# Gecko-Node.net
KiCad netlist of a schematic drawn in EAGLE
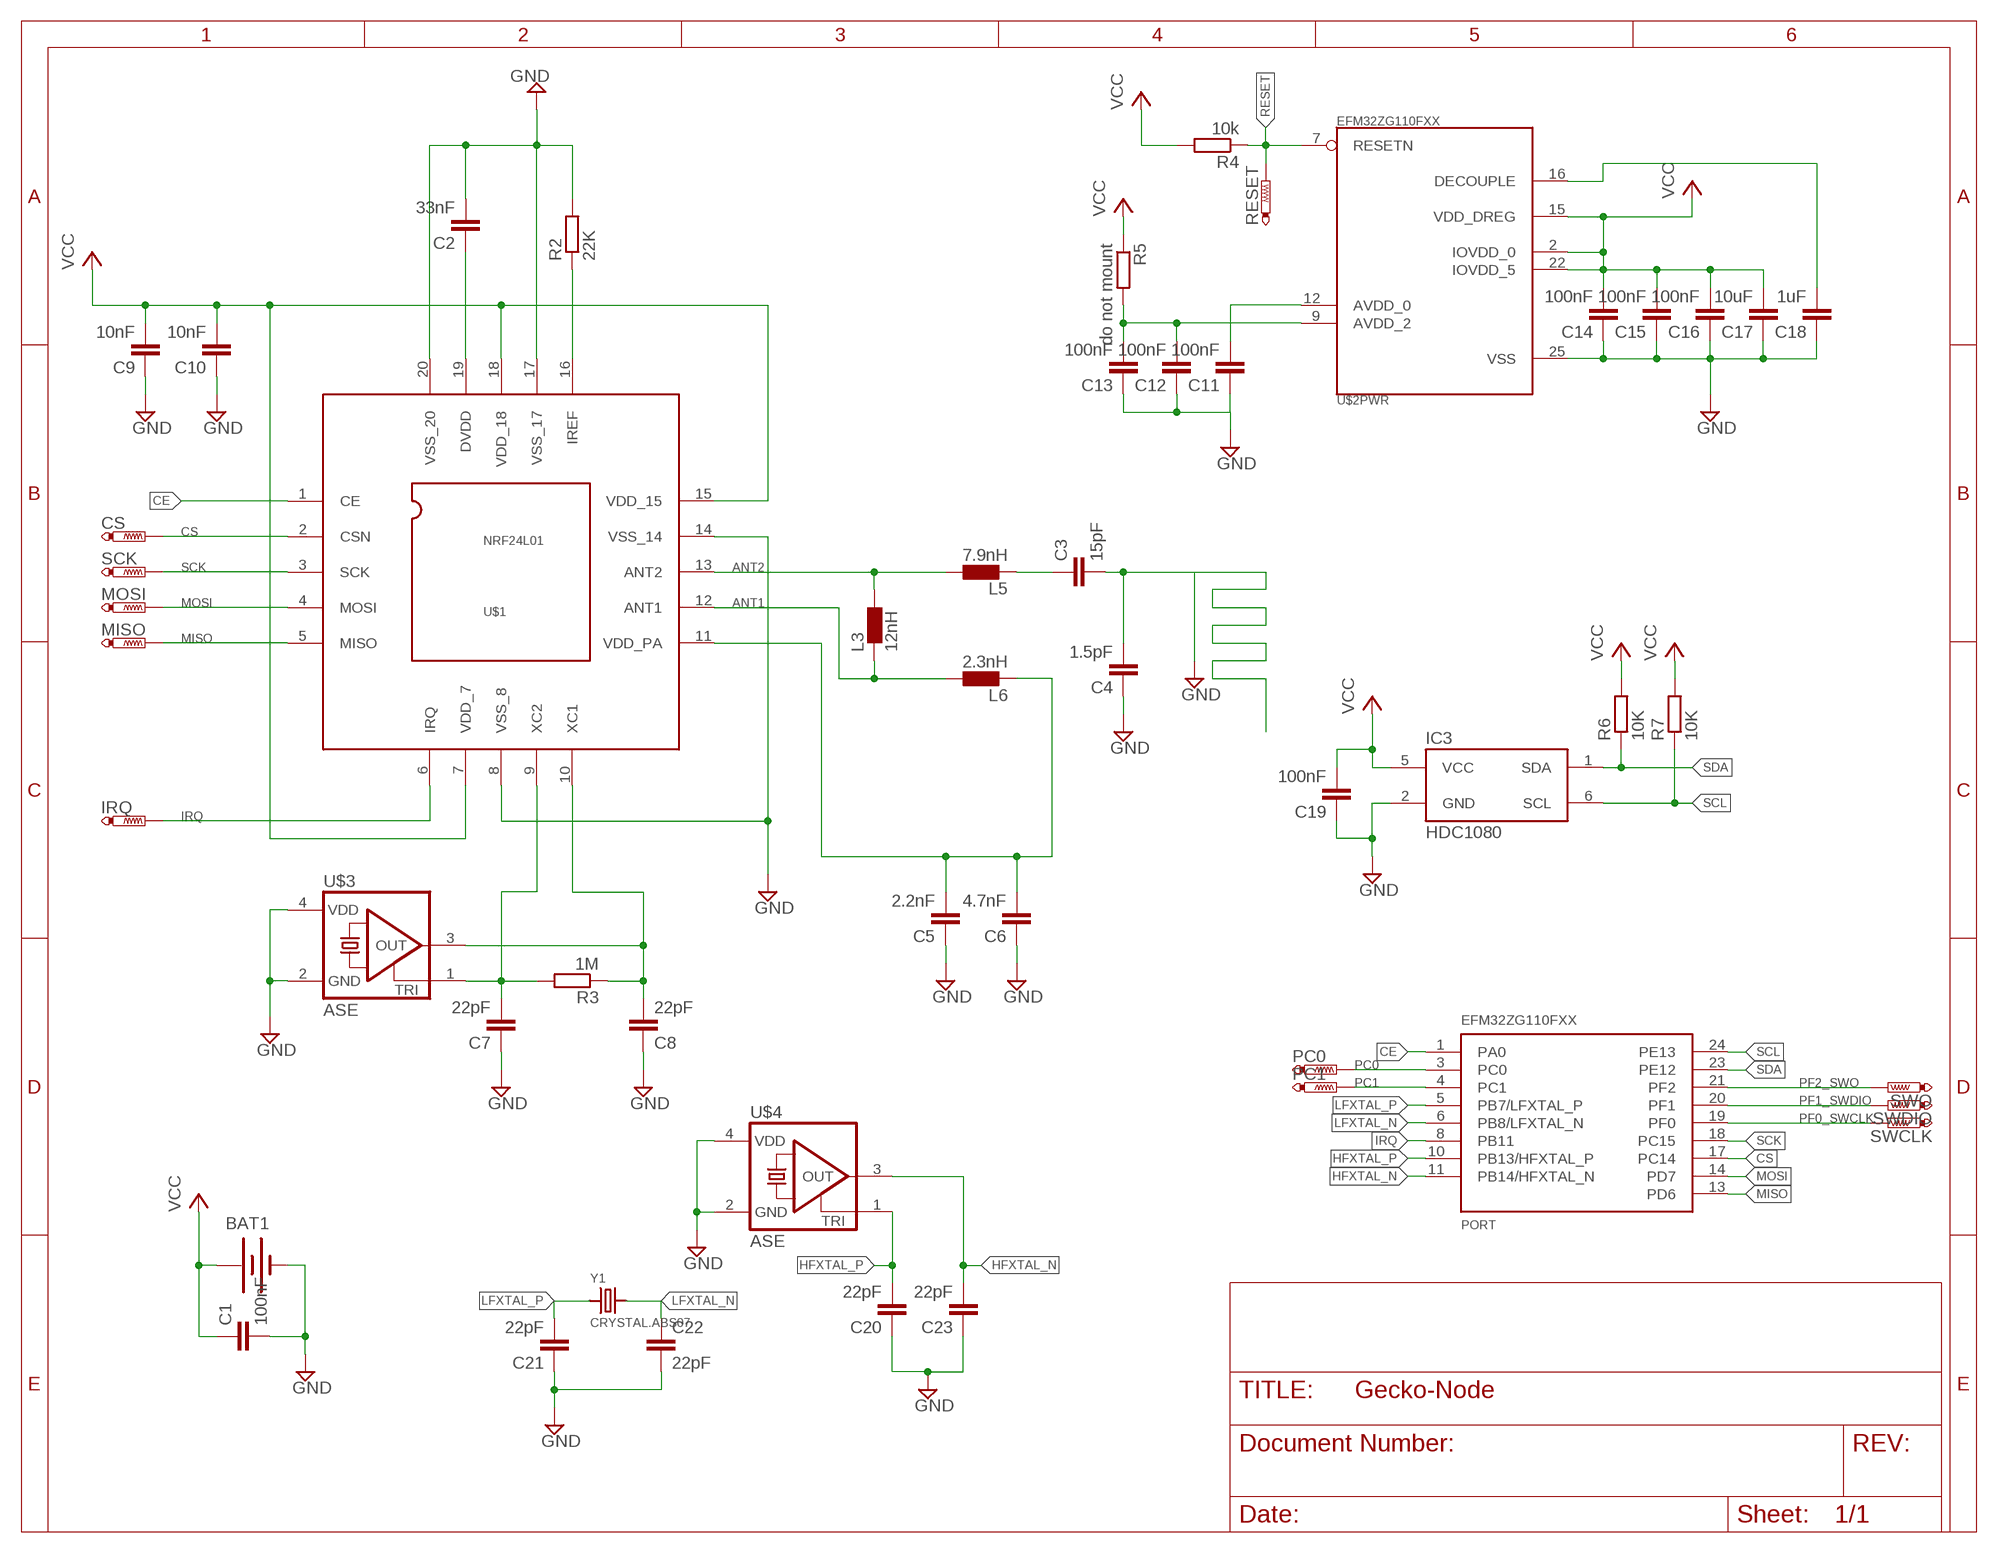
[diagram p0: schematic, sheet 1]

(export (version "E")
  (design (tool "Eeschema 10.0.6"))
  (components
    (comp (ref "BAT1")
      (value "LINX-BAT-HLD-00120SMD")
      (footprint "eagle-import:BATTCON_20MM")
      (libsource (lib "eagle-import") (part "LINX-BAT-HLD-00120SMD"))
    )
    (comp (ref "C1")
      (value "100nF")
      (footprint "eagle-import:C0603")
      (libsource (lib "eagle-import") (part "C-EUC0603"))
    )
    (comp (ref "C2")
      (value "33nF")
      (footprint "eagle-import:C0603")
      (libsource (lib "eagle-import") (part "C-EUC0603"))
    )
    (comp (ref "C3")
      (value "15pF")
      (footprint "eagle-import:C0603")
      (libsource (lib "eagle-import") (part "C-EUC0603"))
    )
    (comp (ref "C4")
      (value "1.5pF")
      (footprint "eagle-import:C0603")
      (libsource (lib "eagle-import") (part "C-EUC0603"))
    )
    (comp (ref "C5")
      (value "2.2nF")
      (footprint "eagle-import:C0603")
      (libsource (lib "eagle-import") (part "C-EUC0603"))
    )
    (comp (ref "C6")
      (value "4.7nF")
      (footprint "eagle-import:C0603")
      (libsource (lib "eagle-import") (part "C-EUC0603"))
    )
    (comp (ref "C7")
      (value "22pF")
      (footprint "eagle-import:C0603")
      (libsource (lib "eagle-import") (part "C-EUC0603"))
    )
    (comp (ref "C8")
      (value "22pF")
      (footprint "eagle-import:C0603")
      (libsource (lib "eagle-import") (part "C-EUC0603"))
    )
    (comp (ref "C9")
      (value "10nF")
      (footprint "eagle-import:C0603")
      (libsource (lib "eagle-import") (part "C-EUC0603"))
    )
    (comp (ref "C10")
      (value "10nF")
      (footprint "eagle-import:C0603")
      (libsource (lib "eagle-import") (part "C-EUC0603"))
    )
    (comp (ref "C11")
      (value "100nF")
      (footprint "eagle-import:C0603")
      (libsource (lib "eagle-import") (part "C-EUC0603"))
    )
    (comp (ref "C12")
      (value "100nF")
      (footprint "eagle-import:C0603")
      (libsource (lib "eagle-import") (part "C-EUC0603"))
    )
    (comp (ref "C13")
      (value "100nF")
      (footprint "eagle-import:C0603")
      (libsource (lib "eagle-import") (part "C-EUC0603"))
    )
    (comp (ref "C14")
      (value "100nF")
      (footprint "eagle-import:C0603")
      (libsource (lib "eagle-import") (part "C-EUC0603"))
    )
    (comp (ref "C15")
      (value "100nF")
      (footprint "eagle-import:C0603")
      (libsource (lib "eagle-import") (part "C-EUC0603"))
    )
    (comp (ref "C16")
      (value "100nF")
      (footprint "eagle-import:C0603")
      (libsource (lib "eagle-import") (part "C-EUC0603"))
    )
    (comp (ref "C17")
      (value "10uF")
      (footprint "eagle-import:C0603")
      (libsource (lib "eagle-import") (part "C-EUC0603"))
    )
    (comp (ref "C18")
      (value "1uF")
      (footprint "eagle-import:C0603")
      (libsource (lib "eagle-import") (part "C-EUC0603"))
    )
    (comp (ref "C19")
      (value "100nF")
      (footprint "eagle-import:C0603")
      (libsource (lib "eagle-import") (part "C-EUC0603"))
    )
    (comp (ref "C20")
      (value "22pF")
      (footprint "eagle-import:C0603")
      (libsource (lib "eagle-import") (part "C-EUC0603"))
    )
    (comp (ref "C21")
      (value "22pF")
      (footprint "eagle-import:C0603")
      (libsource (lib "eagle-import") (part "C-EUC0603"))
    )
    (comp (ref "C22")
      (value "22pF")
      (footprint "eagle-import:C0603")
      (libsource (lib "eagle-import") (part "C-EUC0603"))
    )
    (comp (ref "C23")
      (value "22pF")
      (footprint "eagle-import:C0603")
      (libsource (lib "eagle-import") (part "C-EUC0603"))
    )
    (comp (ref "CS")
      (value "PTR1TP08R")
      (footprint "eagle-import:TP08R")
      (libsource (lib "eagle-import") (part "PTR1TP08R"))
    )
    (comp (ref "IC3")
      (value "HDC1080")
      (footprint "eagle-import:WSON6")
      (libsource (lib "eagle-import") (part "HDC1080"))
    )
    (comp (ref "IRQ")
      (value "PTR1TP08R")
      (footprint "eagle-import:TP08R")
      (libsource (lib "eagle-import") (part "PTR1TP08R"))
    )
    (comp (ref "L3")
      (value "12nH")
      (footprint "eagle-import:R0603")
      (libsource (lib "eagle-import") (part "L"))
    )
    (comp (ref "L5")
      (value "7.9nH")
      (footprint "eagle-import:R0603")
      (libsource (lib "eagle-import") (part "L"))
    )
    (comp (ref "L6")
      (value "2.3nH")
      (footprint "eagle-import:R0603")
      (libsource (lib "eagle-import") (part "L"))
    )
    (comp (ref "MISO")
      (value "PTR1TP08R")
      (footprint "eagle-import:TP08R")
      (libsource (lib "eagle-import") (part "PTR1TP08R"))
    )
    (comp (ref "MOSI")
      (value "PTR1TP08R")
      (footprint "eagle-import:TP08R")
      (libsource (lib "eagle-import") (part "PTR1TP08R"))
    )
    (comp (ref "PC0")
      (value "PTR1TP08R")
      (footprint "eagle-import:TP08R")
      (libsource (lib "eagle-import") (part "PTR1TP08R"))
    )
    (comp (ref "PC1")
      (value "PTR1TP08R")
      (footprint "eagle-import:TP08R")
      (libsource (lib "eagle-import") (part "PTR1TP08R"))
    )
    (comp (ref "R2")
      (value "22K")
      (footprint "eagle-import:R0603")
      (libsource (lib "eagle-import") (part "R-EU_R0603"))
    )
    (comp (ref "R3")
      (value "1M")
      (footprint "eagle-import:R0603")
      (libsource (lib "eagle-import") (part "R-EU_R0603"))
    )
    (comp (ref "R4")
      (value "10k")
      (footprint "eagle-import:R0603")
      (libsource (lib "eagle-import") (part "R-EU_R0603"))
    )
    (comp (ref "R5")
      (value "do not mount")
      (footprint "eagle-import:R0603")
      (libsource (lib "eagle-import") (part "R-EU_R0603"))
    )
    (comp (ref "R6")
      (value "10K")
      (footprint "eagle-import:R0603")
      (libsource (lib "eagle-import") (part "R-EU_R0603"))
    )
    (comp (ref "R7")
      (value "10K")
      (footprint "eagle-import:R0603")
      (libsource (lib "eagle-import") (part "R-EU_R0603"))
    )
    (comp (ref "RESET")
      (value "PTR1TP08R")
      (footprint "eagle-import:TP08R")
      (libsource (lib "eagle-import") (part "PTR1TP08R"))
    )
    (comp (ref "SCK")
      (value "PTR1TP08R")
      (footprint "eagle-import:TP08R")
      (libsource (lib "eagle-import") (part "PTR1TP08R"))
    )
    (comp (ref "SWCLK")
      (value "PTR1TP08R")
      (footprint "eagle-import:TP08R")
      (libsource (lib "eagle-import") (part "PTR1TP08R"))
    )
    (comp (ref "SWDIO")
      (value "PTR1TP08R")
      (footprint "eagle-import:TP08R")
      (libsource (lib "eagle-import") (part "PTR1TP08R"))
    )
    (comp (ref "SWO")
      (value "PTR1TP08R")
      (footprint "eagle-import:TP08R")
      (libsource (lib "eagle-import") (part "PTR1TP08R"))
    )
    (comp (ref "U$1")
      (value "NRF24L01")
      (footprint "eagle-import:QFN20")
      (libsource (lib "eagle-import") (part "NRF24L01"))
    )
    (comp (ref "U$2")
      (value "EFM32ZG110FXX")
      (footprint "eagle-import:QFN24")
      (libsource (lib "eagle-import") (part "EFM32ZG110FXX"))
    )
    (comp (ref "U$3")
      (value "ASE")
      (footprint "eagle-import:ASE")
      (libsource (lib "eagle-import") (part "ASE"))
    )
    (comp (ref "U$4")
      (value "ASE")
      (footprint "eagle-import:ASE")
      (libsource (lib "eagle-import") (part "ASE"))
    )
    (comp (ref "Y1")
      (value "CRYSTAL.ABS07")
      (footprint "eagle-import:ABS07")
      (libsource (lib "eagle-import") (part "CRYSTAL.ABS07"))
    )
  )
  (nets
    (net (code "1") (name "/ANT1") (class "Default")
      (node (ref "L3") (pin "2") (pinfunction "2_2") (pintype "passive"))
      (node (ref "L6") (pin "1") (pinfunction "1_1") (pintype "passive"))
      (node (ref "U$1") (pin "12") (pinfunction "ANT1_12") (pintype "bidirectional"))
    )
    (net (code "2") (name "/ANT2") (class "Default")
      (node (ref "L3") (pin "1") (pinfunction "1_1") (pintype "passive"))
      (node (ref "L5") (pin "1") (pinfunction "1_1") (pintype "passive"))
      (node (ref "U$1") (pin "13") (pinfunction "ANT2_13") (pintype "bidirectional"))
    )
    (net (code "3") (name "/PC0") (class "Default")
      (node (ref "PC0") (pin "TP") (pinfunction "TP_TP") (pintype "input"))
      (node (ref "U$2") (pin "3") (pinfunction "PC0_3") (pintype "bidirectional"))
    )
    (net (code "4") (name "/PC1") (class "Default")
      (node (ref "PC1") (pin "TP") (pinfunction "TP_TP") (pintype "input"))
      (node (ref "U$2") (pin "4") (pinfunction "PC1_4") (pintype "bidirectional"))
    )
    (net (code "5") (name "/PF0_SWCLK") (class "Default")
      (node (ref "SWCLK") (pin "TP") (pinfunction "TP_TP") (pintype "input"))
      (node (ref "U$2") (pin "19") (pinfunction "PF0_19") (pintype "bidirectional"))
    )
    (net (code "6") (name "/PF1_SWDIO") (class "Default")
      (node (ref "SWDIO") (pin "TP") (pinfunction "TP_TP") (pintype "input"))
      (node (ref "U$2") (pin "20") (pinfunction "PF1_20") (pintype "bidirectional"))
    )
    (net (code "7") (name "/PF2_SWO") (class "Default")
      (node (ref "SWO") (pin "TP") (pinfunction "TP_TP") (pintype "input"))
      (node (ref "U$2") (pin "21") (pinfunction "PF2_21") (pintype "bidirectional"))
    )
    (net (code "8") (name "CE") (class "Default")
      (node (ref "U$1") (pin "1") (pinfunction "CE_1") (pintype "bidirectional"))
      (node (ref "U$2") (pin "1") (pinfunction "PA0_1") (pintype "bidirectional"))
    )
    (net (code "9") (name "CS") (class "Default")
      (node (ref "CS") (pin "TP") (pinfunction "TP_TP") (pintype "input"))
      (node (ref "U$1") (pin "2") (pinfunction "CSN_2") (pintype "bidirectional"))
      (node (ref "U$2") (pin "17") (pinfunction "PC14_17") (pintype "bidirectional"))
    )
    (net (code "10") (name "GND") (class "Default")
      (node (ref "BAT1") (pin "2") (pinfunction "-_2") (pintype "power_in"))
      (node (ref "C1") (pin "2") (pinfunction "2_2") (pintype "passive"))
      (node (ref "C10") (pin "1") (pinfunction "1_1") (pintype "passive"))
      (node (ref "C11") (pin "1") (pinfunction "1_1") (pintype "passive"))
      (node (ref "C12") (pin "1") (pinfunction "1_1") (pintype "passive"))
      (node (ref "C13") (pin "1") (pinfunction "1_1") (pintype "passive"))
      (node (ref "C14") (pin "1") (pinfunction "1_1") (pintype "passive"))
      (node (ref "C15") (pin "1") (pinfunction "1_1") (pintype "passive"))
      (node (ref "C16") (pin "1") (pinfunction "1_1") (pintype "passive"))
      (node (ref "C17") (pin "1") (pinfunction "1_1") (pintype "passive"))
      (node (ref "C18") (pin "1") (pinfunction "1_1") (pintype "passive"))
      (node (ref "C19") (pin "1") (pinfunction "1_1") (pintype "passive"))
      (node (ref "C2") (pin "2") (pinfunction "2_2") (pintype "passive"))
      (node (ref "C20") (pin "1") (pinfunction "1_1") (pintype "passive"))
      (node (ref "C21") (pin "1") (pinfunction "1_1") (pintype "passive"))
      (node (ref "C22") (pin "2") (pinfunction "2_2") (pintype "passive"))
      (node (ref "C23") (pin "1") (pinfunction "1_1") (pintype "passive"))
      (node (ref "C3") (pin "2") (pinfunction "2_2") (pintype "passive"))
      (node (ref "C4") (pin "1") (pinfunction "1_1") (pintype "passive"))
      (node (ref "C4") (pin "2") (pinfunction "2_2") (pintype "passive"))
      (node (ref "C5") (pin "1") (pinfunction "1_1") (pintype "passive"))
      (node (ref "C6") (pin "1") (pinfunction "1_1") (pintype "passive"))
      (node (ref "C7") (pin "1") (pinfunction "1_1") (pintype "passive"))
      (node (ref "C8") (pin "1") (pinfunction "1_1") (pintype "passive"))
      (node (ref "C9") (pin "1") (pinfunction "1_1") (pintype "passive"))
      (node (ref "IC3") (pin "2") (pinfunction "GND_2") (pintype "power_in"))
      (node (ref "R2") (pin "2") (pinfunction "2_2") (pintype "passive"))
      (node (ref "U$1") (pin "14") (pinfunction "VSS_14_14") (pintype "bidirectional"))
      (node (ref "U$1") (pin "17") (pinfunction "VSS_17_17") (pintype "bidirectional"))
      (node (ref "U$1") (pin "20") (pinfunction "VSS_20_20") (pintype "bidirectional"))
      (node (ref "U$1") (pin "8") (pinfunction "VSS_8_8") (pintype "bidirectional"))
      (node (ref "U$2") (pin "25") (pinfunction "VSS_25") (pintype "power_in"))
      (node (ref "U$3") (pin "2") (pinfunction "GND_2") (pintype "power_in"))
      (node (ref "U$3") (pin "4") (pinfunction "VDD_4") (pintype "power_in"))
      (node (ref "U$4") (pin "2") (pinfunction "GND_2") (pintype "power_in"))
      (node (ref "U$4") (pin "4") (pinfunction "VDD_4") (pintype "power_in"))
    )
    (net (code "11") (name "HFXTAL_N") (class "Default")
      (node (ref "C23") (pin "2") (pinfunction "2_2") (pintype "passive"))
      (node (ref "U$2") (pin "11") (pinfunction "PB14/HFXTAL_N_11") (pintype "bidirectional"))
      (node (ref "U$4") (pin "3") (pinfunction "OUT_3") (pintype "output"))
    )
    (net (code "12") (name "HFXTAL_P") (class "Default")
      (node (ref "C20") (pin "2") (pinfunction "2_2") (pintype "passive"))
      (node (ref "U$2") (pin "10") (pinfunction "PB13/HFXTAL_P_10") (pintype "bidirectional"))
      (node (ref "U$4") (pin "1") (pinfunction "TRI_1") (pintype "input"))
    )
    (net (code "13") (name "IRQ") (class "Default")
      (node (ref "IRQ") (pin "TP") (pinfunction "TP_TP") (pintype "input"))
      (node (ref "U$1") (pin "6") (pinfunction "IRQ_6") (pintype "bidirectional"))
      (node (ref "U$2") (pin "8") (pinfunction "PB11_8") (pintype "bidirectional"))
    )
    (net (code "14") (name "LFXTAL_N") (class "Default")
      (node (ref "C22") (pin "1") (pinfunction "1_1") (pintype "passive"))
      (node (ref "U$2") (pin "6") (pinfunction "PB8/LFXTAL_N_6") (pintype "bidirectional"))
      (node (ref "Y1") (pin "2") (pinfunction "2_2") (pintype "passive"))
    )
    (net (code "15") (name "LFXTAL_P") (class "Default")
      (node (ref "C21") (pin "2") (pinfunction "2_2") (pintype "passive"))
      (node (ref "U$2") (pin "5") (pinfunction "PB7/LFXTAL_P_5") (pintype "bidirectional"))
      (node (ref "Y1") (pin "1") (pinfunction "1_1") (pintype "passive"))
    )
    (net (code "16") (name "MISO") (class "Default")
      (node (ref "MISO") (pin "TP") (pinfunction "TP_TP") (pintype "input"))
      (node (ref "U$1") (pin "5") (pinfunction "MISO_5") (pintype "bidirectional"))
      (node (ref "U$2") (pin "13") (pinfunction "PD6_13") (pintype "bidirectional"))
    )
    (net (code "17") (name "MOSI") (class "Default")
      (node (ref "MOSI") (pin "TP") (pinfunction "TP_TP") (pintype "input"))
      (node (ref "U$1") (pin "4") (pinfunction "MOSI_4") (pintype "bidirectional"))
      (node (ref "U$2") (pin "14") (pinfunction "PD7_14") (pintype "bidirectional"))
    )
    (net (code "18") (name "Net-(C3-Pad1)") (class "Default")
      (node (ref "C3") (pin "1") (pinfunction "1_1") (pintype "passive"))
      (node (ref "L5") (pin "2") (pinfunction "2_2") (pintype "passive"))
    )
    (net (code "19") (name "Net-(U$1-DVDD)") (class "Default")
      (node (ref "C2") (pin "1") (pinfunction "1_1") (pintype "passive"))
      (node (ref "U$1") (pin "19") (pinfunction "DVDD_19") (pintype "bidirectional"))
    )
    (net (code "20") (name "Net-(U$1-IREF)") (class "Default")
      (node (ref "R2") (pin "1") (pinfunction "1_1") (pintype "passive"))
      (node (ref "U$1") (pin "16") (pinfunction "IREF_16") (pintype "bidirectional"))
    )
    (net (code "21") (name "Net-(U$1-VDD_PA)") (class "Default")
      (node (ref "C5") (pin "2") (pinfunction "2_2") (pintype "passive"))
      (node (ref "C6") (pin "2") (pinfunction "2_2") (pintype "passive"))
      (node (ref "L6") (pin "2") (pinfunction "2_2") (pintype "passive"))
      (node (ref "U$1") (pin "11") (pinfunction "VDD_PA_11") (pintype "bidirectional"))
    )
    (net (code "22") (name "Net-(U$1-XC1)") (class "Default")
      (node (ref "C8") (pin "2") (pinfunction "2_2") (pintype "passive"))
      (node (ref "R3") (pin "1") (pinfunction "1_1") (pintype "passive"))
      (node (ref "U$1") (pin "10") (pinfunction "XC1_10") (pintype "bidirectional"))
      (node (ref "U$3") (pin "3") (pinfunction "OUT_3") (pintype "output"))
    )
    (net (code "23") (name "Net-(U$1-XC2)") (class "Default")
      (node (ref "C7") (pin "2") (pinfunction "2_2") (pintype "passive"))
      (node (ref "R3") (pin "2") (pinfunction "2_2") (pintype "passive"))
      (node (ref "U$1") (pin "9") (pinfunction "XC2_9") (pintype "bidirectional"))
      (node (ref "U$3") (pin "1") (pinfunction "TRI_1") (pintype "input"))
    )
    (net (code "24") (name "Net-(U$2B-AVDD_0)") (class "Default")
      (node (ref "C11") (pin "2") (pinfunction "2_2") (pintype "passive"))
      (node (ref "U$2") (pin "12") (pinfunction "AVDD_0_12") (pintype "power_in"))
    )
    (net (code "25") (name "Net-(U$2B-AVDD_2)") (class "Default")
      (node (ref "C12") (pin "2") (pinfunction "2_2") (pintype "passive"))
      (node (ref "C13") (pin "2") (pinfunction "2_2") (pintype "passive"))
      (node (ref "R5") (pin "2") (pinfunction "2_2") (pintype "passive"))
      (node (ref "U$2") (pin "9") (pinfunction "AVDD_2_9") (pintype "power_in"))
    )
    (net (code "26") (name "Net-(U$2B-DECOUPLE)") (class "Default")
      (node (ref "C18") (pin "2") (pinfunction "2_2") (pintype "passive"))
      (node (ref "U$2") (pin "16") (pinfunction "DECOUPLE_16") (pintype "power_in"))
    )
    (net (code "27") (name "RESET") (class "Default")
      (node (ref "R4") (pin "1") (pinfunction "1_1") (pintype "passive"))
      (node (ref "RESET") (pin "TP") (pinfunction "TP_TP") (pintype "input"))
      (node (ref "U$2") (pin "7") (pinfunction "RESETN_7") (pintype "passive"))
    )
    (net (code "28") (name "SCK") (class "Default")
      (node (ref "SCK") (pin "TP") (pinfunction "TP_TP") (pintype "input"))
      (node (ref "U$1") (pin "3") (pinfunction "SCK_3") (pintype "bidirectional"))
      (node (ref "U$2") (pin "18") (pinfunction "PC15_18") (pintype "bidirectional"))
    )
    (net (code "29") (name "SCL") (class "Default")
      (node (ref "IC3") (pin "6") (pinfunction "SCL_6") (pintype "bidirectional"))
      (node (ref "R7") (pin "1") (pinfunction "1_1") (pintype "passive"))
      (node (ref "U$2") (pin "24") (pinfunction "PE13_24") (pintype "bidirectional"))
    )
    (net (code "30") (name "SDA") (class "Default")
      (node (ref "IC3") (pin "1") (pinfunction "SDA_1") (pintype "bidirectional"))
      (node (ref "R6") (pin "1") (pinfunction "1_1") (pintype "passive"))
      (node (ref "U$2") (pin "23") (pinfunction "PE12_23") (pintype "bidirectional"))
    )
    (net (code "31") (name "VCC") (class "Default")
      (node (ref "BAT1") (pin "1") (pinfunction "+_1") (pintype "power_in"))
      (node (ref "BAT1") (pin "3") (pinfunction "+_3") (pintype "power_in"))
      (node (ref "C1") (pin "1") (pinfunction "1_1") (pintype "passive"))
      (node (ref "C10") (pin "2") (pinfunction "2_2") (pintype "passive"))
      (node (ref "C14") (pin "2") (pinfunction "2_2") (pintype "passive"))
      (node (ref "C15") (pin "2") (pinfunction "2_2") (pintype "passive"))
      (node (ref "C16") (pin "2") (pinfunction "2_2") (pintype "passive"))
      (node (ref "C17") (pin "2") (pinfunction "2_2") (pintype "passive"))
      (node (ref "C19") (pin "2") (pinfunction "2_2") (pintype "passive"))
      (node (ref "C9") (pin "2") (pinfunction "2_2") (pintype "passive"))
      (node (ref "IC3") (pin "5") (pinfunction "VCC_5") (pintype "power_in"))
      (node (ref "R4") (pin "2") (pinfunction "2_2") (pintype "passive"))
      (node (ref "R5") (pin "1") (pinfunction "1_1") (pintype "passive"))
      (node (ref "R6") (pin "2") (pinfunction "2_2") (pintype "passive"))
      (node (ref "R7") (pin "2") (pinfunction "2_2") (pintype "passive"))
      (node (ref "U$1") (pin "15") (pinfunction "VDD_15_15") (pintype "bidirectional"))
      (node (ref "U$1") (pin "18") (pinfunction "VDD_18_18") (pintype "bidirectional"))
      (node (ref "U$1") (pin "7") (pinfunction "VDD_7_7") (pintype "bidirectional"))
      (node (ref "U$2") (pin "15") (pinfunction "VDD_DREG_15") (pintype "power_in"))
      (node (ref "U$2") (pin "2") (pinfunction "IOVDD_0_2") (pintype "power_in"))
      (node (ref "U$2") (pin "22") (pinfunction "IOVDD_5_22") (pintype "power_in"))
    )
  )
)
